# avr_programming_shield_Sockets_-_DaveO_v.net
KiCad netlist of a schematic drawn in EAGLE
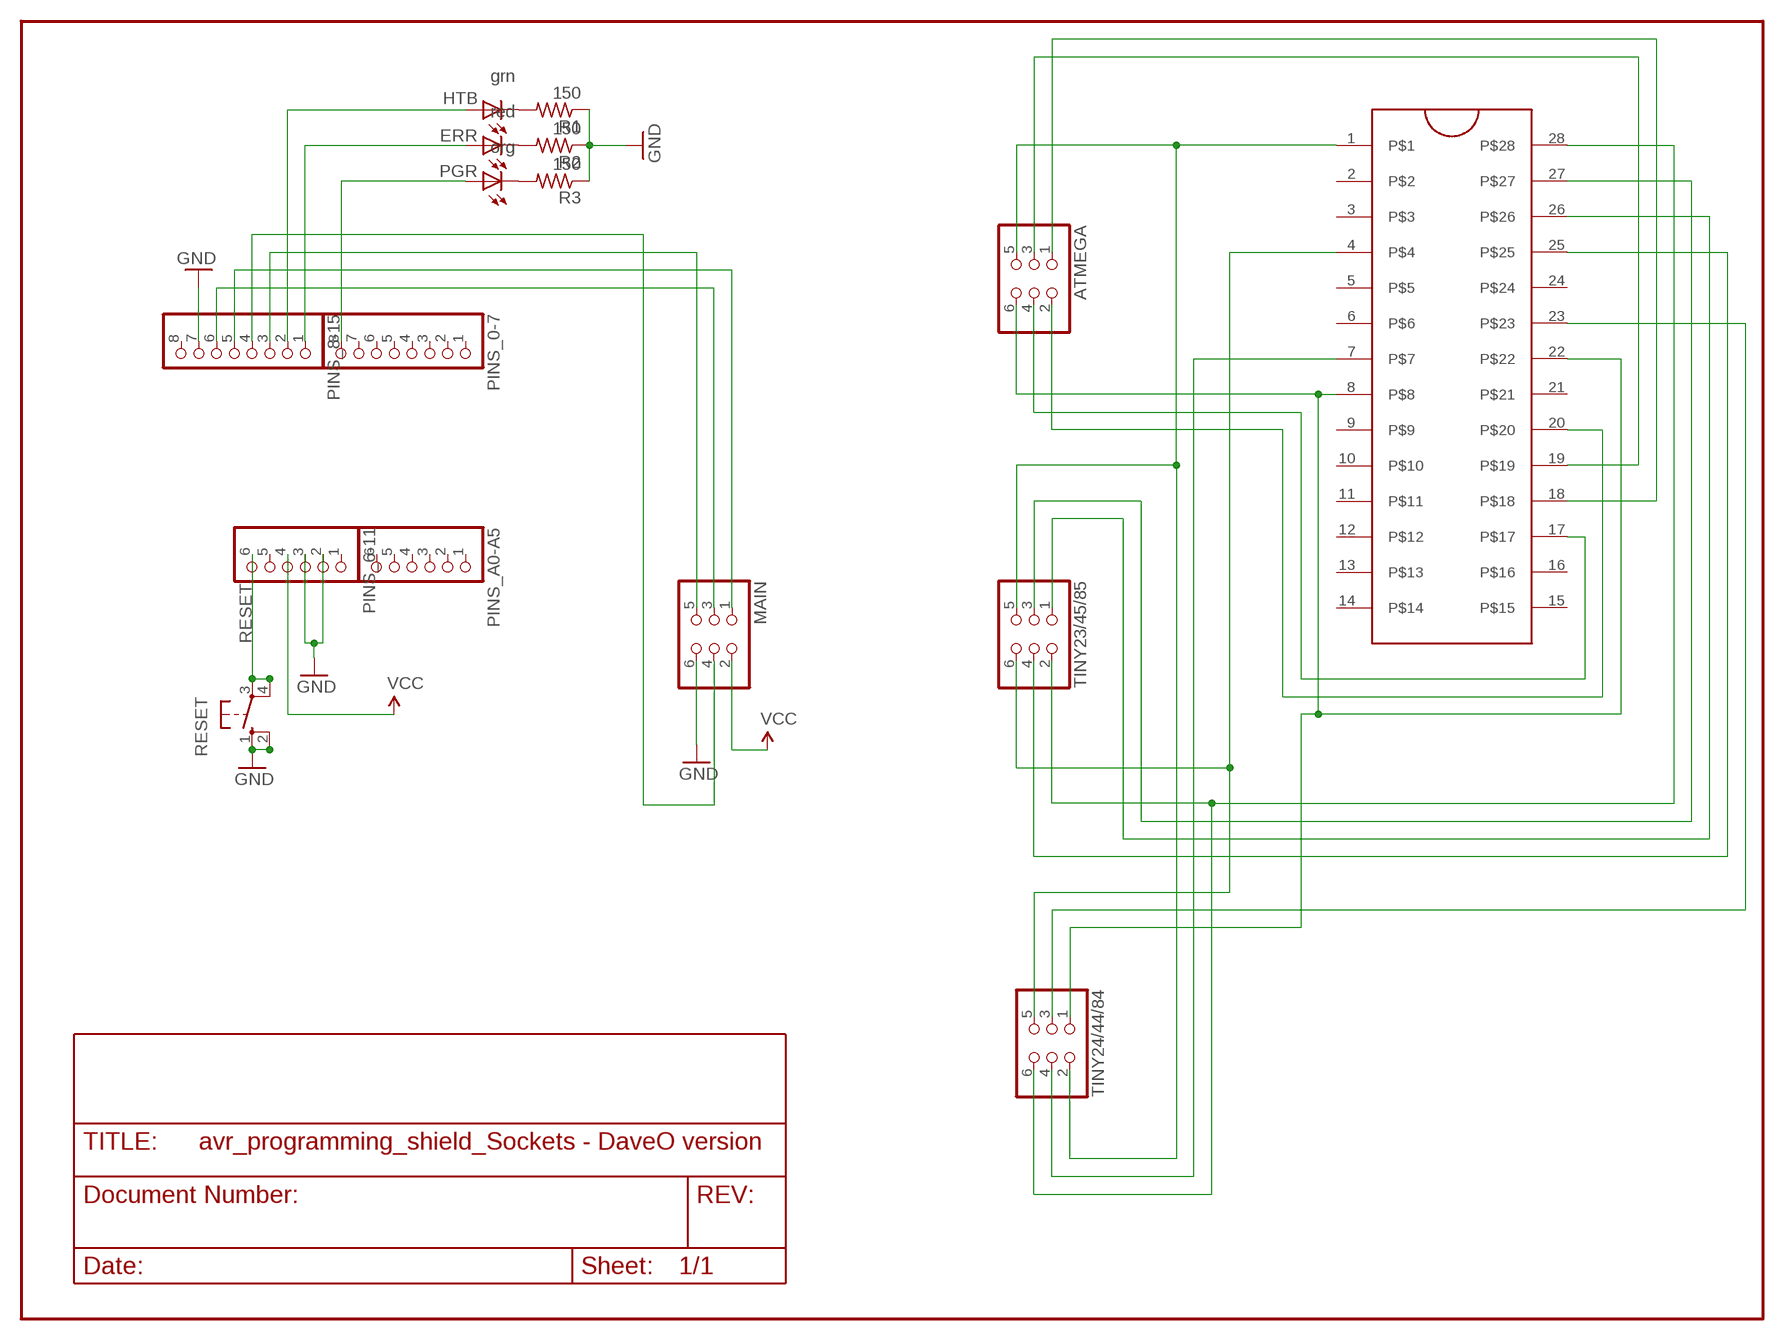
[diagram p0: schematic, sheet 1]

(export (version "E")
  (design (tool "Eeschema 10.0.6"))
  (components
    (comp (ref "ATMEGA")
      (value "PINHD-2X3")
      (footprint "eagle-import:2X03")
      (libsource (lib "eagle-import") (part "PINHD-2X3"))
    )
    (comp (ref "ERR")
      (value "red")
      (footprint "eagle-import:LED3MM")
      (libsource (lib "eagle-import") (part "LED3MM"))
    )
    (comp (ref "HTB")
      (value "grn")
      (footprint "eagle-import:LED3MM")
      (libsource (lib "eagle-import") (part "LED3MM"))
    )
    (comp (ref "MAIN")
      (value "PINHD-2X3")
      (footprint "eagle-import:2X03")
      (libsource (lib "eagle-import") (part "PINHD-2X3"))
    )
    (comp (ref "PGR")
      (value "org")
      (footprint "eagle-import:LED3MM")
      (libsource (lib "eagle-import") (part "LED3MM"))
    )
    (comp (ref "PINS_0-7")
      (value "PINHD-1X8BIG")
      (footprint "eagle-import:1X08-BIG")
      (libsource (lib "eagle-import") (part "PINHD-1X8BIG"))
    )
    (comp (ref "PINS_6-11")
      (value "PINHD-1X6B")
      (footprint "eagle-import:1X06-BIG")
      (libsource (lib "eagle-import") (part "PINHD-1X6B"))
    )
    (comp (ref "PINS_8-15")
      (value "PINHD-1X8BIG")
      (footprint "eagle-import:1X08-BIG")
      (libsource (lib "eagle-import") (part "PINHD-1X8BIG"))
    )
    (comp (ref "PINS_A0-A5")
      (value "PINHD-1X6B")
      (footprint "eagle-import:1X06-BIG")
      (libsource (lib "eagle-import") (part "PINHD-1X6B"))
    )
    (comp (ref "R1")
      (value "150")
      (footprint "eagle-import:0204V")
      (libsource (lib "eagle-import") (part "R-US_0204/2V"))
    )
    (comp (ref "R2")
      (value "150")
      (footprint "eagle-import:0204V")
      (libsource (lib "eagle-import") (part "R-US_0204/2V"))
    )
    (comp (ref "R3")
      (value "150")
      (footprint "eagle-import:0204V")
      (libsource (lib "eagle-import") (part "R-US_0204/2V"))
    )
    (comp (ref "RESET")
      (value "10-XX")
      (footprint "eagle-import:B3F-10XX")
      (libsource (lib "eagle-import") (part "10-XX"))
    )
    (comp (ref "TINY23/45/85")
      (value "PINHD-2X3")
      (footprint "eagle-import:2X03")
      (libsource (lib "eagle-import") (part "PINHD-2X3"))
    )
    (comp (ref "TINY24/44/84")
      (value "PINHD-2X3")
      (footprint "eagle-import:2X03")
      (libsource (lib "eagle-import") (part "PINHD-2X3"))
    )
    (comp (ref "U$2")
      (value "ZIFSOCKET-28-3ZIFFSOCKET-28-3")
      (footprint "eagle-import:DIL28-3-ZIF_SOCKET")
      (libsource (lib "eagle-import") (part "ZIFSOCKET-28-3ZIFFSOCKET-28-3"))
    )
  )
  (nets
    (net (code "1") (name "/RESET") (class "Default")
      (node (ref "PINS_6-11") (pin "6") (pinfunction "6_6") (pintype "passive"))
      (node (ref "RESET") (pin "3") (pinfunction "P_3") (pintype "passive"))
      (node (ref "RESET") (pin "4") (pinfunction "P1_4") (pintype "passive"))
    )
    (net (code "2") (name "GND") (class "Default")
      (node (ref "MAIN") (pin "6") (pinfunction "6_6") (pintype "passive"))
      (node (ref "PINS_6-11") (pin "2") (pinfunction "2_2") (pintype "passive"))
      (node (ref "PINS_6-11") (pin "3") (pinfunction "3_3") (pintype "passive"))
      (node (ref "PINS_8-15") (pin "7") (pinfunction "7_7") (pintype "passive"))
      (node (ref "R1") (pin "1") (pinfunction "1_1") (pintype "passive"))
      (node (ref "R2") (pin "1") (pinfunction "1_1") (pintype "passive"))
      (node (ref "R3") (pin "1") (pinfunction "1_1") (pintype "passive"))
      (node (ref "RESET") (pin "1") (pinfunction "S_1") (pintype "passive"))
      (node (ref "RESET") (pin "2") (pinfunction "S1_2") (pintype "passive"))
    )
    (net (code "3") (name "Net-(ERR-C)") (class "Default")
      (node (ref "ERR") (pin "K") (pinfunction "C_K") (pintype "passive"))
      (node (ref "R2") (pin "2") (pinfunction "2_2") (pintype "passive"))
    )
    (net (code "4") (name "Net-(ERR-PadA)") (class "Default")
      (node (ref "ERR") (pin "A") (pinfunction "A_A") (pintype "passive"))
      (node (ref "PINS_8-15") (pin "1") (pinfunction "1_1") (pintype "passive"))
    )
    (net (code "5") (name "Net-(HTB-C)") (class "Default")
      (node (ref "HTB") (pin "K") (pinfunction "C_K") (pintype "passive"))
      (node (ref "R1") (pin "2") (pinfunction "2_2") (pintype "passive"))
    )
    (net (code "6") (name "Net-(HTB-PadA)") (class "Default")
      (node (ref "HTB") (pin "A") (pinfunction "A_A") (pintype "passive"))
      (node (ref "PINS_8-15") (pin "2") (pinfunction "2_2") (pintype "passive"))
    )
    (net (code "7") (name "Net-(MAIN-Pad1)") (class "Default")
      (node (ref "MAIN") (pin "1") (pinfunction "1_1") (pintype "passive"))
      (node (ref "PINS_8-15") (pin "5") (pinfunction "5_5") (pintype "passive"))
    )
    (net (code "8") (name "Net-(MAIN-Pad3)") (class "Default")
      (node (ref "MAIN") (pin "3") (pinfunction "3_3") (pintype "passive"))
      (node (ref "PINS_8-15") (pin "6") (pinfunction "6_6") (pintype "passive"))
    )
    (net (code "9") (name "Net-(MAIN-Pad4)") (class "Default")
      (node (ref "MAIN") (pin "4") (pinfunction "4_4") (pintype "passive"))
      (node (ref "PINS_8-15") (pin "4") (pinfunction "4_4") (pintype "passive"))
    )
    (net (code "10") (name "Net-(MAIN-Pad5)") (class "Default")
      (node (ref "MAIN") (pin "5") (pinfunction "5_5") (pintype "passive"))
      (node (ref "PINS_8-15") (pin "3") (pinfunction "3_3") (pintype "passive"))
    )
    (net (code "11") (name "Net-(PGR-C)") (class "Default")
      (node (ref "PGR") (pin "K") (pinfunction "C_K") (pintype "passive"))
      (node (ref "R3") (pin "2") (pinfunction "2_2") (pintype "passive"))
    )
    (net (code "12") (name "Net-(PGR-PadA)") (class "Default")
      (node (ref "PGR") (pin "A") (pinfunction "A_A") (pintype "passive"))
      (node (ref "PINS_0-7") (pin "8") (pinfunction "8_8") (pintype "passive"))
    )
    (net (code "13") (name "Net-(U$2-P$1)") (class "Default")
      (node (ref "ATMEGA") (pin "5") (pinfunction "5_5") (pintype "passive"))
      (node (ref "TINY23/45/85") (pin "5") (pinfunction "5_5") (pintype "passive"))
      (node (ref "TINY24/44/84") (pin "2") (pinfunction "2_2") (pintype "passive"))
      (node (ref "U$2") (pin "1") (pinfunction "P$1_1") (pintype "bidirectional"))
    )
    (net (code "14") (name "Net-(U$2-P$4)") (class "Default")
      (node (ref "TINY23/45/85") (pin "6") (pinfunction "6_6") (pintype "passive"))
      (node (ref "TINY24/44/84") (pin "5") (pinfunction "5_5") (pintype "passive"))
      (node (ref "U$2") (pin "4") (pinfunction "P$4_4") (pintype "bidirectional"))
    )
    (net (code "15") (name "Net-(U$2-P$7)") (class "Default")
      (node (ref "TINY24/44/84") (pin "4") (pinfunction "4_4") (pintype "passive"))
      (node (ref "U$2") (pin "7") (pinfunction "P$7_7") (pintype "bidirectional"))
    )
    (net (code "16") (name "Net-(U$2-P$17)") (class "Default")
      (node (ref "ATMEGA") (pin "4") (pinfunction "4_4") (pintype "passive"))
      (node (ref "U$2") (pin "17") (pinfunction "P$17_17") (pintype "bidirectional"))
    )
    (net (code "17") (name "Net-(U$2-P$18)") (class "Default")
      (node (ref "ATMEGA") (pin "1") (pinfunction "1_1") (pintype "passive"))
      (node (ref "U$2") (pin "18") (pinfunction "P$18_18") (pintype "bidirectional"))
    )
    (net (code "18") (name "Net-(U$2-P$19)") (class "Default")
      (node (ref "ATMEGA") (pin "3") (pinfunction "3_3") (pintype "passive"))
      (node (ref "U$2") (pin "19") (pinfunction "P$19_19") (pintype "bidirectional"))
    )
    (net (code "19") (name "Net-(U$2-P$20)") (class "Default")
      (node (ref "ATMEGA") (pin "2") (pinfunction "2_2") (pintype "passive"))
      (node (ref "U$2") (pin "20") (pinfunction "P$20_20") (pintype "bidirectional"))
    )
    (net (code "20") (name "Net-(U$2-P$22)") (class "Default")
      (node (ref "ATMEGA") (pin "6") (pinfunction "6_6") (pintype "passive"))
      (node (ref "TINY24/44/84") (pin "1") (pinfunction "1_1") (pintype "passive"))
      (node (ref "U$2") (pin "22") (pinfunction "P$22_22") (pintype "bidirectional"))
      (node (ref "U$2") (pin "8") (pinfunction "P$8_8") (pintype "bidirectional"))
    )
    (net (code "21") (name "Net-(U$2-P$23)") (class "Default")
      (node (ref "TINY24/44/84") (pin "3") (pinfunction "3_3") (pintype "passive"))
      (node (ref "U$2") (pin "23") (pinfunction "P$23_23") (pintype "bidirectional"))
    )
    (net (code "22") (name "Net-(U$2-P$25)") (class "Default")
      (node (ref "TINY23/45/85") (pin "4") (pinfunction "4_4") (pintype "passive"))
      (node (ref "U$2") (pin "25") (pinfunction "P$25_25") (pintype "bidirectional"))
    )
    (net (code "23") (name "Net-(U$2-P$26)") (class "Default")
      (node (ref "TINY23/45/85") (pin "1") (pinfunction "1_1") (pintype "passive"))
      (node (ref "U$2") (pin "26") (pinfunction "P$26_26") (pintype "bidirectional"))
    )
    (net (code "24") (name "Net-(U$2-P$27)") (class "Default")
      (node (ref "TINY23/45/85") (pin "3") (pinfunction "3_3") (pintype "passive"))
      (node (ref "U$2") (pin "27") (pinfunction "P$27_27") (pintype "bidirectional"))
    )
    (net (code "25") (name "Net-(U$2-P$28)") (class "Default")
      (node (ref "TINY23/45/85") (pin "2") (pinfunction "2_2") (pintype "passive"))
      (node (ref "TINY24/44/84") (pin "6") (pinfunction "6_6") (pintype "passive"))
      (node (ref "U$2") (pin "28") (pinfunction "P$28_28") (pintype "bidirectional"))
    )
    (net (code "26") (name "VCC") (class "Default")
      (node (ref "MAIN") (pin "2") (pinfunction "2_2") (pintype "passive"))
      (node (ref "PINS_6-11") (pin "4") (pinfunction "4_4") (pintype "passive"))
    )
    (net (code "27") (name "unconnected-(PINS_0-7-Pad1)") (class "Default")
      (node (ref "PINS_0-7") (pin "1") (pinfunction "1_1") (pintype "passive"))
    )
    (net (code "28") (name "unconnected-(PINS_0-7-Pad2)") (class "Default")
      (node (ref "PINS_0-7") (pin "2") (pinfunction "2_2") (pintype "passive"))
    )
    (net (code "29") (name "unconnected-(PINS_0-7-Pad3)") (class "Default")
      (node (ref "PINS_0-7") (pin "3") (pinfunction "3_3") (pintype "passive"))
    )
    (net (code "30") (name "unconnected-(PINS_0-7-Pad4)") (class "Default")
      (node (ref "PINS_0-7") (pin "4") (pinfunction "4_4") (pintype "passive"))
    )
    (net (code "31") (name "unconnected-(PINS_0-7-Pad5)") (class "Default")
      (node (ref "PINS_0-7") (pin "5") (pinfunction "5_5") (pintype "passive"))
    )
    (net (code "32") (name "unconnected-(PINS_0-7-Pad6)") (class "Default")
      (node (ref "PINS_0-7") (pin "6") (pinfunction "6_6") (pintype "passive"))
    )
    (net (code "33") (name "unconnected-(PINS_0-7-Pad7)") (class "Default")
      (node (ref "PINS_0-7") (pin "7") (pinfunction "7_7") (pintype "passive"))
    )
    (net (code "34") (name "unconnected-(PINS_6-11-Pad1)") (class "Default")
      (node (ref "PINS_6-11") (pin "1") (pinfunction "1_1") (pintype "passive"))
    )
    (net (code "35") (name "unconnected-(PINS_6-11-Pad5)") (class "Default")
      (node (ref "PINS_6-11") (pin "5") (pinfunction "5_5") (pintype "passive"))
    )
    (net (code "36") (name "unconnected-(PINS_8-15-Pad8)") (class "Default")
      (node (ref "PINS_8-15") (pin "8") (pinfunction "8_8") (pintype "passive"))
    )
    (net (code "37") (name "unconnected-(PINS_A0-A5-Pad1)") (class "Default")
      (node (ref "PINS_A0-A5") (pin "1") (pinfunction "1_1") (pintype "passive"))
    )
    (net (code "38") (name "unconnected-(PINS_A0-A5-Pad2)") (class "Default")
      (node (ref "PINS_A0-A5") (pin "2") (pinfunction "2_2") (pintype "passive"))
    )
    (net (code "39") (name "unconnected-(PINS_A0-A5-Pad3)") (class "Default")
      (node (ref "PINS_A0-A5") (pin "3") (pinfunction "3_3") (pintype "passive"))
    )
    (net (code "40") (name "unconnected-(PINS_A0-A5-Pad4)") (class "Default")
      (node (ref "PINS_A0-A5") (pin "4") (pinfunction "4_4") (pintype "passive"))
    )
    (net (code "41") (name "unconnected-(PINS_A0-A5-Pad5)") (class "Default")
      (node (ref "PINS_A0-A5") (pin "5") (pinfunction "5_5") (pintype "passive"))
    )
    (net (code "42") (name "unconnected-(PINS_A0-A5-Pad6)") (class "Default")
      (node (ref "PINS_A0-A5") (pin "6") (pinfunction "6_6") (pintype "passive"))
    )
    (net (code "43") (name "unconnected-(U$2-P$2-Pad2)") (class "Default")
      (node (ref "U$2") (pin "2") (pinfunction "P$2_2") (pintype "bidirectional"))
    )
    (net (code "44") (name "unconnected-(U$2-P$3-Pad3)") (class "Default")
      (node (ref "U$2") (pin "3") (pinfunction "P$3_3") (pintype "bidirectional"))
    )
    (net (code "45") (name "unconnected-(U$2-P$5-Pad5)") (class "Default")
      (node (ref "U$2") (pin "5") (pinfunction "P$5_5") (pintype "bidirectional"))
    )
    (net (code "46") (name "unconnected-(U$2-P$6-Pad6)") (class "Default")
      (node (ref "U$2") (pin "6") (pinfunction "P$6_6") (pintype "bidirectional"))
    )
    (net (code "47") (name "unconnected-(U$2-P$9-Pad9)") (class "Default")
      (node (ref "U$2") (pin "9") (pinfunction "P$9_9") (pintype "bidirectional"))
    )
    (net (code "48") (name "unconnected-(U$2-P$10-Pad10)") (class "Default")
      (node (ref "U$2") (pin "10") (pinfunction "P$10_10") (pintype "bidirectional"))
    )
    (net (code "49") (name "unconnected-(U$2-P$11-Pad11)") (class "Default")
      (node (ref "U$2") (pin "11") (pinfunction "P$11_11") (pintype "bidirectional"))
    )
    (net (code "50") (name "unconnected-(U$2-P$12-Pad12)") (class "Default")
      (node (ref "U$2") (pin "12") (pinfunction "P$12_12") (pintype "bidirectional"))
    )
    (net (code "51") (name "unconnected-(U$2-P$13-Pad13)") (class "Default")
      (node (ref "U$2") (pin "13") (pinfunction "P$13_13") (pintype "bidirectional"))
    )
    (net (code "52") (name "unconnected-(U$2-P$14-Pad14)") (class "Default")
      (node (ref "U$2") (pin "14") (pinfunction "P$14_14") (pintype "bidirectional"))
    )
    (net (code "53") (name "unconnected-(U$2-P$15-Pad15)") (class "Default")
      (node (ref "U$2") (pin "15") (pinfunction "P$15_15") (pintype "bidirectional"))
    )
    (net (code "54") (name "unconnected-(U$2-P$16-Pad16)") (class "Default")
      (node (ref "U$2") (pin "16") (pinfunction "P$16_16") (pintype "bidirectional"))
    )
    (net (code "55") (name "unconnected-(U$2-P$21-Pad21)") (class "Default")
      (node (ref "U$2") (pin "21") (pinfunction "P$21_21") (pintype "bidirectional"))
    )
    (net (code "56") (name "unconnected-(U$2-P$24-Pad24)") (class "Default")
      (node (ref "U$2") (pin "24") (pinfunction "P$24_24") (pintype "bidirectional"))
    )
  )
)
